# ESP32-DEVKITC-32D.net
KiCad netlist of a schematic drawn in Altium Designer
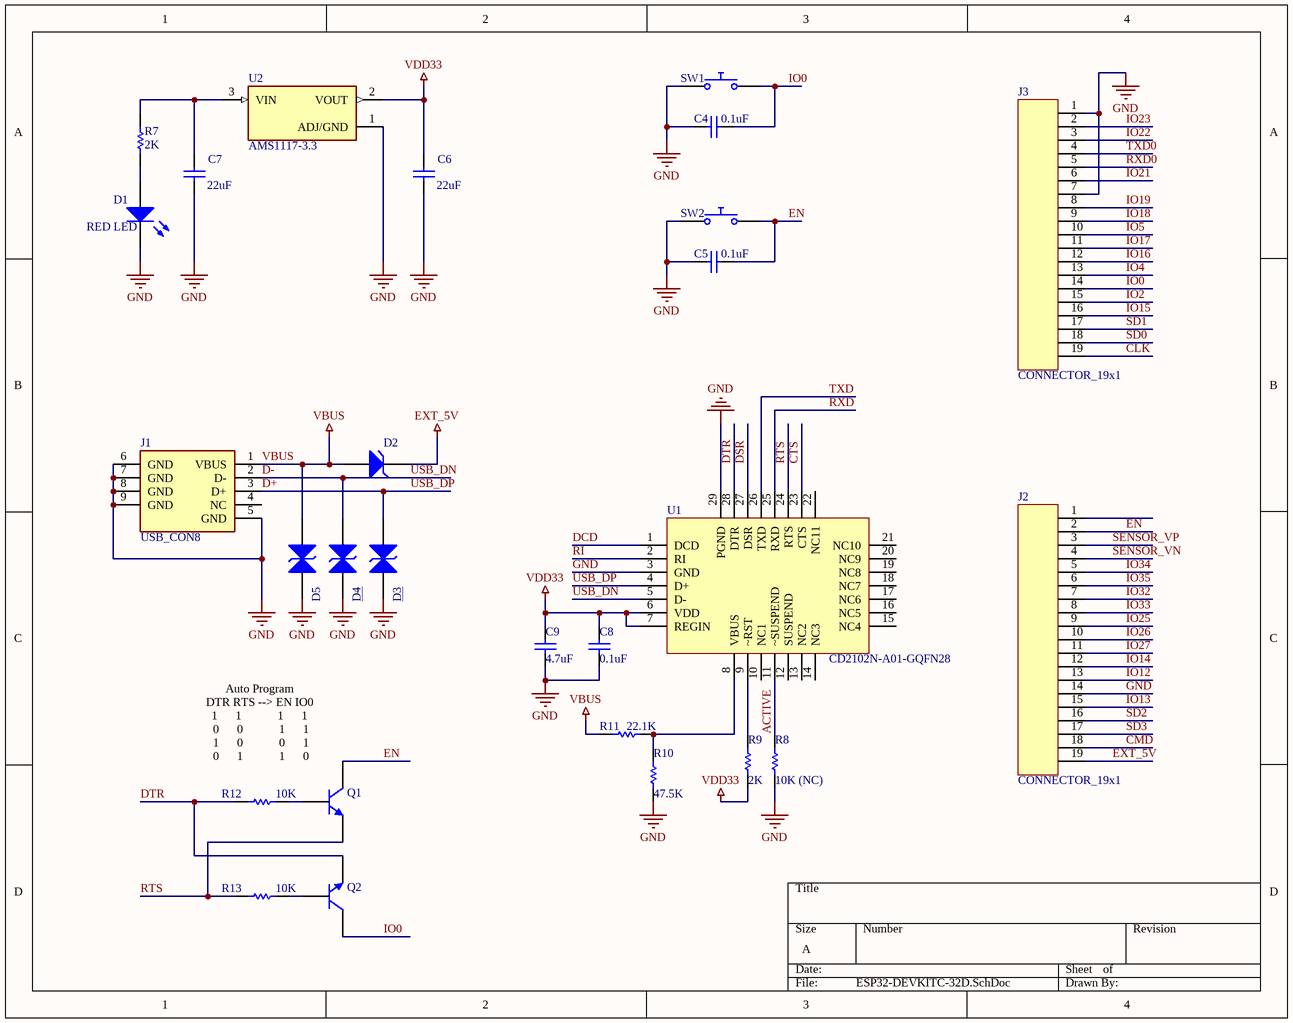
[diagram p0: ESP32-DEVKITC-32D.SchDoc]

(export (version "E")
  (design (tool "Eeschema 10.0.6"))
  (components
    (comp (ref "C4")
      (value "0.1uF")
      (description "Capacitor")
      (libsource (lib "Simulation Generic Components") (part "Capacitor"))
    )
    (comp (ref "C5")
      (value "0.1uF")
      (description "Capacitor")
      (libsource (lib "Simulation Generic Components") (part "Capacitor"))
    )
    (comp (ref "C6")
      (value "22uF")
      (description "Capacitor")
      (libsource (lib "Simulation Generic Components") (part "Capacitor"))
    )
    (comp (ref "C7")
      (value "22uF")
      (description "Capacitor")
      (libsource (lib "Simulation Generic Components") (part "Capacitor"))
    )
    (comp (ref "C8")
      (value "0.1uF")
      (description "Capacitor")
      (libsource (lib "Simulation Generic Components") (part "Capacitor"))
    )
    (comp (ref "C9")
      (value "4.7uF")
      (description "Capacitor")
      (libsource (lib "Simulation Generic Components") (part "Capacitor"))
    )
    (comp (ref "D1")
      (value "RED LED")
      (description "Light-Emitting Diode")
      (libsource (lib "Simulation Generic Components") (part "LED"))
    )
    (comp (ref "D2")
      (value "Zener Diode")
      (libsource (lib "Simulation Generic Components") (part "Zener Diode"))
    )
    (comp (ref "D3")
      (value "Suppressor Dual")
      (libsource (lib "Simulation Generic Components") (part "Suppressor Dual"))
    )
    (comp (ref "D4")
      (value "Suppressor Dual")
      (libsource (lib "Simulation Generic Components") (part "Suppressor Dual"))
    )
    (comp (ref "D5")
      (value "Suppressor Dual")
      (libsource (lib "Simulation Generic Components") (part "Suppressor Dual"))
    )
    (comp (ref "J1") (value "USB_CON8") (libsource (lib "USB Connector") (part "USB_CON8")))
    (comp (ref "J2")
      (value "CONNECTOR_19x1")
      (footprint "HDR1X19")
      (description "Header, 19-Pin")
      (fields (field (name "PUBLISHER") "Altium Limited"))
      (libsource (lib "Miscellaneous Connectors") (part "Header 19"))
    )
    (comp (ref "J3")
      (value "CONNECTOR_19x1")
      (footprint "HDR1X19")
      (description "Header, 19-Pin")
      (fields (field (name "PUBLISHER") "Altium Limited"))
      (libsource (lib "Miscellaneous Connectors") (part "Header 19"))
    )
    (comp (ref "Q1")
      (value "Bipolar  NPN 3 Pins  Transistor   Gummel-Poon Model")
      (libsource (lib "Simulation Generic Components") (part "BJT NPN_GP"))
    )
    (comp (ref "Q2")
      (value "Bipolar  NPN 3 Pins  Transistor   Gummel-Poon Model")
      (libsource (lib "Simulation Generic Components") (part "BJT NPN_GP"))
    )
    (comp (ref "R7")
      (value "2K")
      (description "Resistor")
      (libsource (lib "Simulation Generic Components") (part "Resistor"))
    )
    (comp (ref "R8")
      (value "10K (NC)")
      (description "Resistor")
      (libsource (lib "Simulation Generic Components") (part "Resistor"))
    )
    (comp (ref "R9")
      (value "2K")
      (description "Resistor")
      (libsource (lib "Simulation Generic Components") (part "Resistor"))
    )
    (comp (ref "R10")
      (value "47.5K")
      (description "Resistor")
      (libsource (lib "Simulation Generic Components") (part "Resistor"))
    )
    (comp (ref "R11")
      (value "22.1K")
      (description "Resistor")
      (libsource (lib "Simulation Generic Components") (part "Resistor"))
    )
    (comp (ref "R12")
      (value "10K")
      (description "Resistor")
      (libsource (lib "Simulation Generic Components") (part "Resistor"))
    )
    (comp (ref "R13")
      (value "10K")
      (description "Resistor")
      (libsource (lib "Simulation Generic Components") (part "Resistor"))
    )
    (comp (ref "SW1")
      (value "Push Button Normally Opened")
      (libsource (lib "Simulation Generic Components") (part "Push Button NO"))
    )
    (comp (ref "SW2")
      (value "Push Button Normally Opened")
      (libsource (lib "Simulation Generic Components") (part "Push Button NO"))
    )
    (comp (ref "U1")
      (value "CD2102N-A01-GQFN28")
      (libsource (lib "CD2102N-A01-GQFN28") (part "CD2102N-A01-GQFN28"))
    )
    (comp (ref "U2")
      (value "AMS1117-3.3")
      (footprint "SOT229P700X180-4N")
      (description "Linear Voltage Regulator IC Positive Fixed 1 Output 1A SOT-223-3L")
      (fields (field (name "MF") "UMW"))
      (libsource (lib "AMS1117-3.3") (part "AMS1117-3.3"))
    )
  )
  (nets
    (net (code "1") (name "/ACTIVE") (class "Default")
      (node (ref "R8") (pin "2") (pinfunction "2_2") (pintype "passive"))
      (node (ref "U1") (pin "11") (pinfunction "~SUSPEND_11") (pintype "passive"))
    )
    (net (code "2") (name "/CLK") (class "Default")
      (node (ref "J3") (pin "19") (pinfunction "19_19") (pintype "passive"))
    )
    (net (code "3") (name "/CMD") (class "Default")
      (node (ref "J2") (pin "18") (pinfunction "18_18") (pintype "passive"))
    )
    (net (code "4") (name "/CTS") (class "Default")
      (node (ref "U1") (pin "23") (pinfunction "CTS_23") (pintype "passive"))
    )
    (net (code "5") (name "/D+") (class "Default")
      (node (ref "D3") (pin "2") (pinfunction "2_2") (pintype "passive"))
      (node (ref "J1") (pin "3") (pinfunction "D+_3") (pintype "passive"))
      (node (ref "U1") (pin "4") (pinfunction "D+_4") (pintype "passive"))
    )
    (net (code "6") (name "/D-") (class "Default")
      (node (ref "D4") (pin "2") (pinfunction "2_2") (pintype "passive"))
      (node (ref "J1") (pin "2") (pinfunction "D-_2") (pintype "passive"))
      (node (ref "U1") (pin "5") (pinfunction "D-_5") (pintype "passive"))
    )
    (net (code "7") (name "/DCD") (class "Default")
      (node (ref "U1") (pin "1") (pinfunction "DCD_1") (pintype "passive"))
    )
    (net (code "8") (name "/DSR") (class "Default")
      (node (ref "U1") (pin "27") (pinfunction "DSR_27") (pintype "passive"))
    )
    (net (code "9") (name "/DTR") (class "Default")
      (node (ref "Q2") (pin "3") (pinfunction "E_3") (pintype "passive"))
      (node (ref "R12") (pin "2") (pinfunction "2_2") (pintype "passive"))
      (node (ref "U1") (pin "28") (pinfunction "DTR_28") (pintype "passive"))
    )
    (net (code "10") (name "/EN") (class "Default")
      (node (ref "C5") (pin "2") (pinfunction "2_2") (pintype "passive"))
      (node (ref "J2") (pin "2") (pinfunction "2_2") (pintype "passive"))
      (node (ref "Q1") (pin "1") (pinfunction "C_1") (pintype "passive"))
      (node (ref "SW2") (pin "2") (pinfunction "2_2") (pintype "passive"))
    )
    (net (code "11") (name "/IO0") (class "Default")
      (node (ref "C4") (pin "2") (pinfunction "2_2") (pintype "passive"))
      (node (ref "J3") (pin "14") (pinfunction "14_14") (pintype "passive"))
      (node (ref "Q2") (pin "1") (pinfunction "C_1") (pintype "passive"))
      (node (ref "SW1") (pin "2") (pinfunction "2_2") (pintype "passive"))
    )
    (net (code "12") (name "/IO2") (class "Default")
      (node (ref "J3") (pin "15") (pinfunction "15_15") (pintype "passive"))
    )
    (net (code "13") (name "/IO4") (class "Default")
      (node (ref "J3") (pin "13") (pinfunction "13_13") (pintype "passive"))
    )
    (net (code "14") (name "/IO5") (class "Default")
      (node (ref "J3") (pin "10") (pinfunction "10_10") (pintype "passive"))
    )
    (net (code "15") (name "/IO12") (class "Default")
      (node (ref "J2") (pin "13") (pinfunction "13_13") (pintype "passive"))
    )
    (net (code "16") (name "/IO13") (class "Default")
      (node (ref "J2") (pin "15") (pinfunction "15_15") (pintype "passive"))
    )
    (net (code "17") (name "/IO14") (class "Default")
      (node (ref "J2") (pin "12") (pinfunction "12_12") (pintype "passive"))
    )
    (net (code "18") (name "/IO15") (class "Default")
      (node (ref "J3") (pin "16") (pinfunction "16_16") (pintype "passive"))
    )
    (net (code "19") (name "/IO16") (class "Default")
      (node (ref "J3") (pin "12") (pinfunction "12_12") (pintype "passive"))
    )
    (net (code "20") (name "/IO17") (class "Default")
      (node (ref "J3") (pin "11") (pinfunction "11_11") (pintype "passive"))
    )
    (net (code "21") (name "/IO18") (class "Default")
      (node (ref "J3") (pin "9") (pinfunction "9_9") (pintype "passive"))
    )
    (net (code "22") (name "/IO19") (class "Default")
      (node (ref "J3") (pin "8") (pinfunction "8_8") (pintype "passive"))
    )
    (net (code "23") (name "/IO21") (class "Default")
      (node (ref "J3") (pin "6") (pinfunction "6_6") (pintype "passive"))
    )
    (net (code "24") (name "/IO22") (class "Default")
      (node (ref "J3") (pin "3") (pinfunction "3_3") (pintype "passive"))
    )
    (net (code "25") (name "/IO23") (class "Default")
      (node (ref "J3") (pin "2") (pinfunction "2_2") (pintype "passive"))
    )
    (net (code "26") (name "/IO25") (class "Default")
      (node (ref "J2") (pin "9") (pinfunction "9_9") (pintype "passive"))
    )
    (net (code "27") (name "/IO26") (class "Default")
      (node (ref "J2") (pin "10") (pinfunction "10_10") (pintype "passive"))
    )
    (net (code "28") (name "/IO27") (class "Default")
      (node (ref "J2") (pin "11") (pinfunction "11_11") (pintype "passive"))
    )
    (net (code "29") (name "/IO32") (class "Default")
      (node (ref "J2") (pin "7") (pinfunction "7_7") (pintype "passive"))
    )
    (net (code "30") (name "/IO33") (class "Default")
      (node (ref "J2") (pin "8") (pinfunction "8_8") (pintype "passive"))
    )
    (net (code "31") (name "/IO34") (class "Default")
      (node (ref "J2") (pin "5") (pinfunction "5_5") (pintype "passive"))
    )
    (net (code "32") (name "/IO35") (class "Default")
      (node (ref "J2") (pin "6") (pinfunction "6_6") (pintype "passive"))
    )
    (net (code "33") (name "/RI") (class "Default")
      (node (ref "U1") (pin "2") (pinfunction "RI_2") (pintype "passive"))
    )
    (net (code "34") (name "/RTS") (class "Default")
      (node (ref "Q1") (pin "3") (pinfunction "E_3") (pintype "passive"))
      (node (ref "R13") (pin "2") (pinfunction "2_2") (pintype "passive"))
      (node (ref "U1") (pin "24") (pinfunction "RTS_24") (pintype "passive"))
    )
    (net (code "35") (name "/RXD") (class "Default")
      (node (ref "U1") (pin "25") (pinfunction "RXD_25") (pintype "passive"))
    )
    (net (code "36") (name "/RXD0") (class "Default")
      (node (ref "J3") (pin "5") (pinfunction "5_5") (pintype "passive"))
    )
    (net (code "37") (name "/SD0") (class "Default")
      (node (ref "J3") (pin "18") (pinfunction "18_18") (pintype "passive"))
    )
    (net (code "38") (name "/SD1") (class "Default")
      (node (ref "J3") (pin "17") (pinfunction "17_17") (pintype "passive"))
    )
    (net (code "39") (name "/SD2") (class "Default")
      (node (ref "J2") (pin "16") (pinfunction "16_16") (pintype "passive"))
    )
    (net (code "40") (name "/SD3") (class "Default")
      (node (ref "J2") (pin "17") (pinfunction "17_17") (pintype "passive"))
    )
    (net (code "41") (name "/SENSOR_VN") (class "Default")
      (node (ref "J2") (pin "4") (pinfunction "4_4") (pintype "passive"))
    )
    (net (code "42") (name "/SENSOR_VP") (class "Default")
      (node (ref "J2") (pin "3") (pinfunction "3_3") (pintype "passive"))
    )
    (net (code "43") (name "/TXD") (class "Default")
      (node (ref "U1") (pin "26") (pinfunction "TXD_26") (pintype "passive"))
    )
    (net (code "44") (name "/TXD0") (class "Default")
      (node (ref "J3") (pin "4") (pinfunction "4_4") (pintype "passive"))
    )
    (net (code "45") (name "EXT_5V") (class "Default")
      (node (ref "D2") (pin "2") (pinfunction "K_2") (pintype "passive"))
      (node (ref "J2") (pin "19") (pinfunction "19_19") (pintype "passive"))
    )
    (net (code "46") (name "GND") (class "Default")
      (node (ref "C4") (pin "1") (pinfunction "1_1") (pintype "passive"))
      (node (ref "C5") (pin "1") (pinfunction "1_1") (pintype "passive"))
      (node (ref "C6") (pin "1") (pinfunction "1_1") (pintype "passive"))
      (node (ref "C7") (pin "1") (pinfunction "1_1") (pintype "passive"))
      (node (ref "C8") (pin "1") (pinfunction "1_1") (pintype "passive"))
      (node (ref "C9") (pin "1") (pinfunction "1_1") (pintype "passive"))
      (node (ref "D1") (pin "2") (pinfunction "K_2") (pintype "passive"))
      (node (ref "D3") (pin "1") (pinfunction "1_1") (pintype "passive"))
      (node (ref "D4") (pin "1") (pinfunction "1_1") (pintype "passive"))
      (node (ref "D5") (pin "1") (pinfunction "1_1") (pintype "passive"))
      (node (ref "J1") (pin "5") (pinfunction "GND_5") (pintype "passive"))
      (node (ref "J1") (pin "6") (pinfunction "GND_6") (pintype "passive"))
      (node (ref "J1") (pin "7") (pinfunction "GND_7") (pintype "passive"))
      (node (ref "J1") (pin "8") (pinfunction "GND_8") (pintype "passive"))
      (node (ref "J1") (pin "9") (pinfunction "GND_9") (pintype "passive"))
      (node (ref "J2") (pin "14") (pinfunction "14_14") (pintype "passive"))
      (node (ref "J3") (pin "1") (pinfunction "1_1") (pintype "passive"))
      (node (ref "J3") (pin "7") (pinfunction "7_7") (pintype "passive"))
      (node (ref "R10") (pin "1") (pinfunction "1_1") (pintype "passive"))
      (node (ref "R8") (pin "1") (pinfunction "1_1") (pintype "passive"))
      (node (ref "SW1") (pin "1") (pinfunction "1_1") (pintype "passive"))
      (node (ref "SW2") (pin "1") (pinfunction "1_1") (pintype "passive"))
      (node (ref "U1") (pin "29") (pinfunction "PGND_29") (pintype "passive"))
      (node (ref "U1") (pin "3") (pinfunction "GND_3") (pintype "passive"))
      (node (ref "U2") (pin "1") (pinfunction "ADJ/GND_1") (pintype "power_in"))
    )
    (net (code "47") (name "Net-(D1-A)") (class "Default")
      (node (ref "D1") (pin "1") (pinfunction "A_1") (pintype "passive"))
      (node (ref "R7") (pin "1") (pinfunction "1_1") (pintype "passive"))
    )
    (net (code "48") (name "Net-(Q1-B)") (class "Default")
      (node (ref "Q1") (pin "2") (pinfunction "B_2") (pintype "passive"))
      (node (ref "R12") (pin "1") (pinfunction "1_1") (pintype "passive"))
    )
    (net (code "49") (name "Net-(Q2-B)") (class "Default")
      (node (ref "Q2") (pin "2") (pinfunction "B_2") (pintype "passive"))
      (node (ref "R13") (pin "1") (pinfunction "1_1") (pintype "passive"))
    )
    (net (code "50") (name "Net-(U1-VBUS)") (class "Default")
      (node (ref "R10") (pin "2") (pinfunction "2_2") (pintype "passive"))
      (node (ref "R11") (pin "1") (pinfunction "1_1") (pintype "passive"))
      (node (ref "U1") (pin "8") (pinfunction "VBUS_8") (pintype "passive"))
    )
    (net (code "51") (name "Net-(U1-~RST)") (class "Default")
      (node (ref "R9") (pin "2") (pinfunction "2_2") (pintype "passive"))
      (node (ref "U1") (pin "9") (pinfunction "~RST_9") (pintype "passive"))
    )
    (net (code "52") (name "Net-(U2-VIN)") (class "Default")
      (node (ref "C7") (pin "2") (pinfunction "2_2") (pintype "passive"))
      (node (ref "R7") (pin "2") (pinfunction "2_2") (pintype "passive"))
      (node (ref "U2") (pin "3") (pinfunction "VIN_3") (pintype "input"))
    )
    (net (code "53") (name "VBUS") (class "Default")
      (node (ref "D2") (pin "1") (pinfunction "A_1") (pintype "passive"))
      (node (ref "D5") (pin "2") (pinfunction "2_2") (pintype "passive"))
      (node (ref "J1") (pin "1") (pinfunction "VBUS_1") (pintype "passive"))
      (node (ref "R11") (pin "2") (pinfunction "2_2") (pintype "passive"))
    )
    (net (code "54") (name "VDD33") (class "Default")
      (node (ref "C6") (pin "2") (pinfunction "2_2") (pintype "passive"))
      (node (ref "C8") (pin "2") (pinfunction "2_2") (pintype "passive"))
      (node (ref "C9") (pin "2") (pinfunction "2_2") (pintype "passive"))
      (node (ref "R9") (pin "1") (pinfunction "1_1") (pintype "passive"))
      (node (ref "U1") (pin "6") (pinfunction "VDD_6") (pintype "passive"))
      (node (ref "U1") (pin "7") (pinfunction "REGIN_7") (pintype "passive"))
      (node (ref "U2") (pin "2") (pinfunction "VOUT_2") (pintype "output"))
    )
    (net (code "55") (name "unconnected-(J1-NC-Pad4)") (class "Default")
      (node (ref "J1") (pin "4") (pinfunction "NC_4") (pintype "passive"))
    )
    (net (code "56") (name "unconnected-(J2-Pad1)") (class "Default")
      (node (ref "J2") (pin "1") (pinfunction "1_1") (pintype "passive"))
    )
    (net (code "57") (name "unconnected-(U1-NC1-Pad10)") (class "Default")
      (node (ref "U1") (pin "10") (pinfunction "NC1_10") (pintype "passive"))
    )
    (net (code "58") (name "unconnected-(U1-NC2-Pad13)") (class "Default")
      (node (ref "U1") (pin "13") (pinfunction "NC2_13") (pintype "passive"))
    )
    (net (code "59") (name "unconnected-(U1-NC3-Pad14)") (class "Default")
      (node (ref "U1") (pin "14") (pinfunction "NC3_14") (pintype "passive"))
    )
    (net (code "60") (name "unconnected-(U1-NC4-Pad15)") (class "Default")
      (node (ref "U1") (pin "15") (pinfunction "NC4_15") (pintype "passive"))
    )
    (net (code "61") (name "unconnected-(U1-NC5-Pad16)") (class "Default")
      (node (ref "U1") (pin "16") (pinfunction "NC5_16") (pintype "passive"))
    )
    (net (code "62") (name "unconnected-(U1-NC6-Pad17)") (class "Default")
      (node (ref "U1") (pin "17") (pinfunction "NC6_17") (pintype "passive"))
    )
    (net (code "63") (name "unconnected-(U1-NC7-Pad18)") (class "Default")
      (node (ref "U1") (pin "18") (pinfunction "NC7_18") (pintype "passive"))
    )
    (net (code "64") (name "unconnected-(U1-NC8-Pad19)") (class "Default")
      (node (ref "U1") (pin "19") (pinfunction "NC8_19") (pintype "passive"))
    )
    (net (code "65") (name "unconnected-(U1-NC9-Pad20)") (class "Default")
      (node (ref "U1") (pin "20") (pinfunction "NC9_20") (pintype "passive"))
    )
    (net (code "66") (name "unconnected-(U1-NC10-Pad21)") (class "Default")
      (node (ref "U1") (pin "21") (pinfunction "NC10_21") (pintype "passive"))
    )
    (net (code "67") (name "unconnected-(U1-NC11-Pad22)") (class "Default")
      (node (ref "U1") (pin "22") (pinfunction "NC11_22") (pintype "passive"))
    )
    (net (code "68") (name "unconnected-(U1-SUSPEND-Pad12)") (class "Default")
      (node (ref "U1") (pin "12") (pinfunction "SUSPEND_12") (pintype "passive"))
    )
  )
)
